# TSAL.net
KiCad netlist of a schematic drawn in Altium Designer
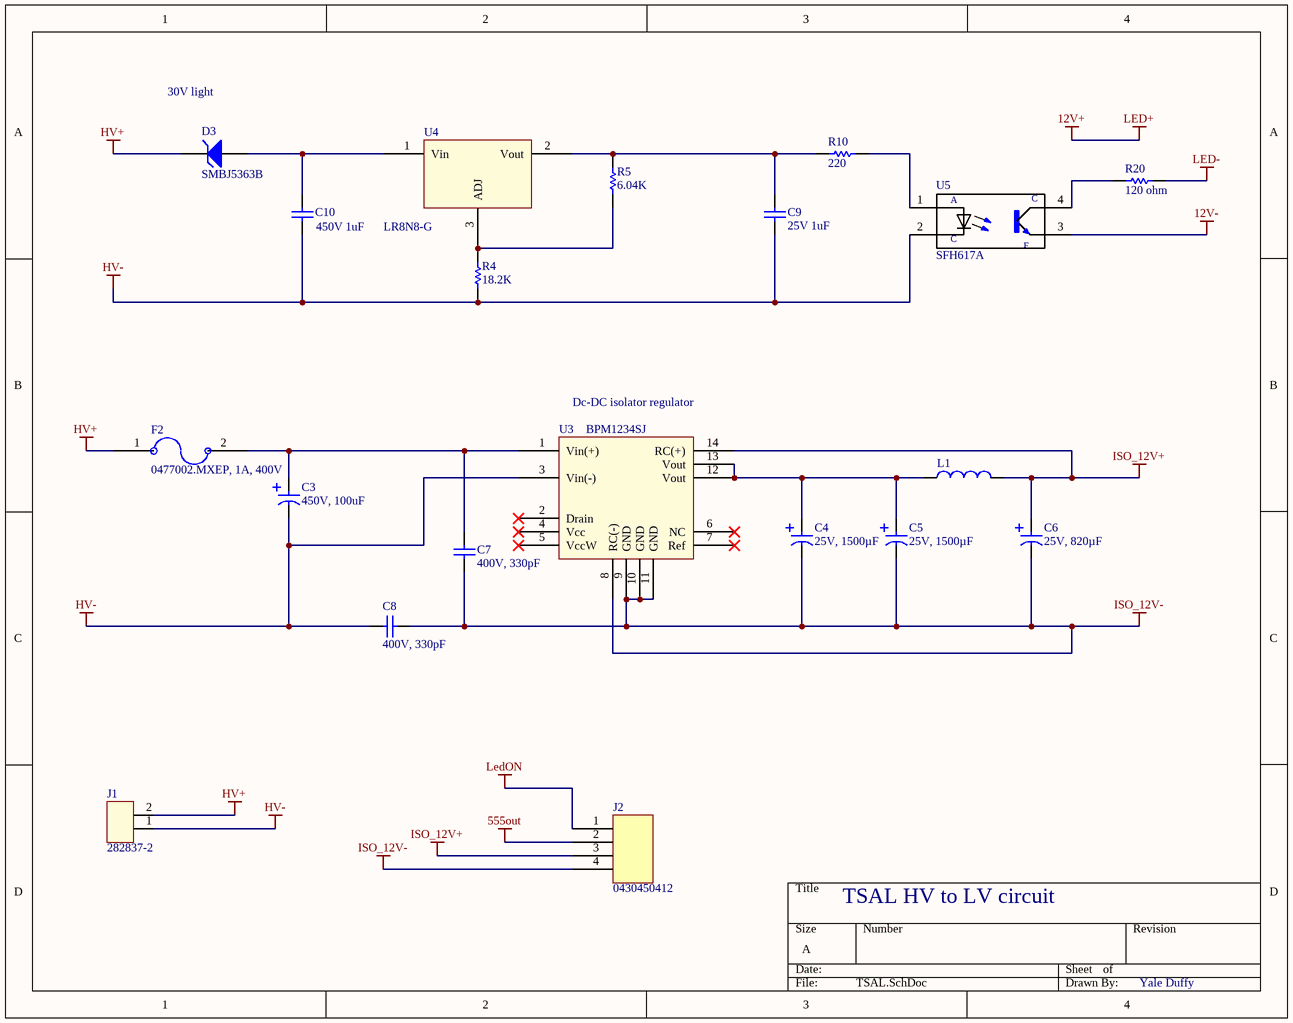
[diagram p0: TSAL.SchDoc]

(export (version "E")
  (design (tool "Eeschema 10.0.6"))
  (components
    (comp (ref "C3")
      (value "450V, 100uF")
      (footprint "450BXW100MEFR18X30")
      (description "Capacitors, Radial, Can, 100µF 450V Aluminum")
      (libsource (lib "schematic") (part "450BXW100MEFR18X30"))
    )
    (comp (ref "C4")
      (value "25V, 1500µF")
      (footprint "25ZLS1500MEFC12.5X20")
      (description "Capacitors, Aluminum Electrolytic, Radial, Can, 1500µF, 25V")
      (libsource (lib "schematic") (part "25ZLS1500MEFC12.5X20"))
    )
    (comp (ref "C5")
      (value "25V, 1500µF")
      (footprint "25ZLS1500MEFC12.5X20")
      (description "Capacitors, Aluminum Electrolytic, Radial, Can, 1500µF, 25V")
      (libsource (lib "schematic") (part "25ZLS1500MEFC12.5X20"))
    )
    (comp (ref "C6")
      (value "25V, 820µF")
      (footprint "ESY827M025AH5AA")
      (description "Capacitors Radial, Can, 820µF 25V Aluminum Electrolytic, 23mOhm @ 100kHz 4000 Hrs @ 105°C")
      (libsource (lib "schematic") (part "ESY827M025AH5AA"))
    )
    (comp (ref "C7")
      (value "400V, 330pF")
      (footprint "DE2B3SA331KN3AY02F")
      (description "Capacitor, 330pF ±10% 400VAC Ceramic Capacitor B Radial, Disc")
      (libsource (lib "schematic") (part "DE2B3SA331KN3AY02F"))
    )
    (comp (ref "C8")
      (value "400V, 330pF")
      (footprint "DE2B3SA331KN3AY02F")
      (description "Capacitor, 330pF ±10% 400VAC Ceramic Capacitor B Radial, Disc")
      (libsource (lib "schematic") (part "DE2B3SA331KN3AY02F"))
    )
    (comp (ref "C9")
      (value "25V 1uF")
      (footprint "C0603C105K3RACTU")
      (description "Capacitor, Ceramic, 1 uF, 25 V, ±10% SMT, 0603")
      (libsource (lib "schematic") (part "C0603C105K3RACTU"))
    )
    (comp (ref "C10")
      (value "450V 1uF")
      (footprint "CKG57KX7T2W105K335JH")
      (description "Decoupling capacitor")
      (libsource (lib "schematic") (part "CKG57KX7T2W105K335JH"))
    )
    (comp (ref "D3")
      (value "SMBJ5363B")
      (footprint "214AA")
      (description "Diode Zener 30V 5W ±5% Surface Mount DO-214AA (SMB)")
      (libsource (lib "schematic") (part "SMBJ5363B"))
    )
    (comp (ref "F2")
      (value "0477002.MXEP, 1A, 400V")
      (footprint "0477002.MXEP")
      (description "Fuse, 2A 500V AC 400V DC Fuse Cartridge, Ceramic Through Hole 5mm x 20mm (Axial)")
      (libsource (lib "schematic") (part "0477002.MXEP"))
    )
    (comp (ref "J1")
      (value "282837-2")
      (footprint "282837-2")
      (description "Connector Terminal Blocks Receptacle 2 Position 5.08mm Solder Straight Thru-Hole 13.5A/Contact")
      (libsource (lib "schematic") (part "282837-2"))
    )
    (comp (ref "J2")
      (value "0430450412")
      (footprint "0430450412")
      (description "Connector Header Through Hole 4 position 0.118\" (3.00mm)")
      (libsource (lib "schematic") (part "0430450412"))
    )
    (comp (ref "L1")
      (value "1267AY-2R2N=P3")
      (footprint "1267AY2R2NP3")
      (description "Shielded Wirewound Inductor, 2.2µH ,7.4A 13.2mOhm Max Nonstandard")
      (libsource (lib "schematic") (part "1267AY-2R2N=P3"))
    )
    (comp (ref "R4")
      (value "18.2K")
      (footprint "Resistor 0603")
      (description "Resistor, 18.2K ohms, 0603, SMD")
      (libsource (lib "schematic") (part "ERJ-3EKF1822V"))
    )
    (comp (ref "R5")
      (value "6.04K")
      (footprint "Resistor 0603")
      (libsource (lib "schematic") (part "ERJ-3EKF6041V"))
    )
    (comp (ref "R10")
      (value "220")
      (footprint "Resistor 0603")
      (description "Resistor, 220 ohm, 0603")
      (libsource (lib "schematic") (part "ERJ-3EKF2200V"))
    )
    (comp (ref "R20")
      (value "120 ohm")
      (footprint "Resistor 0603")
      (description "Resistor, 120 ohms, 0603, SMD")
      (libsource (lib "schematic") (part "ERJ-3EKF1200V"))
    )
    (comp (ref "U3")
      (value "BPM1234SJ")
      (footprint "BPM1234SJ")
      (description "Isolated DC-DC converters, 12 V, 3.4A")
      (libsource (lib "schematic") (part "BPM1234SJ"))
    )
    (comp (ref "U4")
      (value "LR8N8-G")
      (footprint "TO-243AA(SOT-89-3)")
      (description "Voltage Regulator, Linear, input max 480V, output 1.2V - 440V, TO-243AA , SMD")
      (libsource (lib "schematic") (part "LR8N8-G"))
    )
    (comp (ref "U5")
      (value "SFH617A")
      (footprint "SFH617A")
      (description "opto-Isolator")
      (libsource (lib "schematic") (part "SFH617A"))
    )
  )
  (nets
    (net (code "2") (name "12V-") (class "Default")
      (node (ref "U5") (pin "3") (pinfunction "E_3") (pintype "passive"))
    )
    (net (code "3") (name "555out") (class "Default")
      (node (ref "J2") (pin "2") (pinfunction "2_2") (pintype "passive"))
    )
    (net (code "4") (name "HV+") (class "Default")
      (node (ref "D3") (pin "1") (pinfunction "K_1") (pintype "passive"))
      (node (ref "F2") (pin "1") (pinfunction "1_1") (pintype "passive"))
      (node (ref "J1") (pin "2") (pinfunction "2_2") (pintype "passive"))
    )
    (net (code "5") (name "HV-") (class "Default")
      (node (ref "C10") (pin "1") (pintype "passive"))
      (node (ref "C3") (pin "1") (pintype "passive"))
      (node (ref "C8") (pin "2") (pintype "passive"))
      (node (ref "C9") (pin "1") (pintype "passive"))
      (node (ref "J1") (pin "1") (pinfunction "1_1") (pintype "passive"))
      (node (ref "R4") (pin "2") (pinfunction "2_2") (pintype "passive"))
      (node (ref "U3") (pin "3") (pinfunction "Vin(-)_3") (pintype "passive"))
      (node (ref "U5") (pin "2") (pinfunction "C_2") (pintype "passive"))
    )
    (net (code "6") (name "ISO_12V+") (class "Default")
      (node (ref "C6") (pin "2") (pintype "passive"))
      (node (ref "J2") (pin "3") (pinfunction "3_3") (pintype "passive"))
      (node (ref "L1") (pin "2") (pinfunction "2_2") (pintype "passive"))
      (node (ref "U3") (pin "14") (pinfunction "RC(+)_14") (pintype "passive"))
    )
    (net (code "7") (name "ISO_12V-") (class "Default")
      (node (ref "C4") (pin "1") (pintype "passive"))
      (node (ref "C5") (pin "1") (pintype "passive"))
      (node (ref "C6") (pin "1") (pintype "passive"))
      (node (ref "C7") (pin "1") (pintype "passive"))
      (node (ref "C8") (pin "1") (pintype "passive"))
      (node (ref "J2") (pin "4") (pinfunction "4_4") (pintype "passive"))
      (node (ref "U3") (pin "10") (pinfunction "GND_10") (pintype "passive"))
      (node (ref "U3") (pin "11") (pinfunction "GND_11") (pintype "passive"))
      (node (ref "U3") (pin "8") (pinfunction "RC(-)_8") (pintype "passive"))
      (node (ref "U3") (pin "9") (pinfunction "GND_9") (pintype "passive"))
    )
    (net (code "8") (name "LED-") (class "Default")
      (node (ref "R20") (pin "2") (pinfunction "2_2") (pintype "passive"))
    )
    (net (code "9") (name "LedON") (class "Default")
      (node (ref "J2") (pin "1") (pinfunction "1_1") (pintype "passive"))
    )
    (net (code "10") (name "Net-(C4-Pad2)") (class "Default")
      (node (ref "C4") (pin "2") (pintype "passive"))
      (node (ref "C5") (pin "2") (pintype "passive"))
      (node (ref "L1") (pin "1") (pinfunction "1_1") (pintype "passive"))
      (node (ref "U3") (pin "12") (pinfunction "Vout_12") (pintype "passive"))
      (node (ref "U3") (pin "13") (pinfunction "Vout_13") (pintype "passive"))
    )
    (net (code "11") (name "Net-(D3-A)") (class "Default")
      (node (ref "C10") (pin "2") (pintype "passive"))
      (node (ref "D3") (pin "2") (pinfunction "A_2") (pintype "passive"))
      (node (ref "U4") (pin "1") (pinfunction "Vin_1") (pintype "passive"))
    )
    (net (code "12") (name "Net-(U3-Vin(+))") (class "Default")
      (node (ref "C3") (pin "2") (pintype "passive"))
      (node (ref "C7") (pin "2") (pintype "passive"))
      (node (ref "F2") (pin "2") (pinfunction "2_2") (pintype "passive"))
      (node (ref "U3") (pin "1") (pinfunction "Vin(+)_1") (pintype "passive"))
    )
    (net (code "13") (name "Net-(U4-ADJ)") (class "Default")
      (node (ref "R4") (pin "1") (pinfunction "1_1") (pintype "passive"))
      (node (ref "R5") (pin "2") (pinfunction "2_2") (pintype "passive"))
      (node (ref "U4") (pin "3") (pinfunction "ADJ_3") (pintype "passive"))
    )
    (net (code "14") (name "Net-(U4-Vout)") (class "Default")
      (node (ref "C9") (pin "2") (pintype "passive"))
      (node (ref "R10") (pin "1") (pinfunction "1_1") (pintype "passive"))
      (node (ref "R5") (pin "1") (pinfunction "1_1") (pintype "passive"))
      (node (ref "U4") (pin "2") (pinfunction "Vout_2") (pintype "passive"))
    )
    (net (code "15") (name "Net-(U5-A)") (class "Default")
      (node (ref "R10") (pin "2") (pinfunction "2_2") (pintype "passive"))
      (node (ref "U5") (pin "1") (pinfunction "A_1") (pintype "passive"))
    )
    (net (code "16") (name "Net-(U5-CO)") (class "Default")
      (node (ref "R20") (pin "1") (pinfunction "1_1") (pintype "passive"))
      (node (ref "U5") (pin "4") (pinfunction "CO_4") (pintype "passive"))
    )
    (net (code "17") (name "unconnected-(U3-Drain-Pad2)") (class "Default")
      (node (ref "U3") (pin "2") (pinfunction "Drain_2") (pintype "passive+no_connect"))
    )
    (net (code "18") (name "unconnected-(U3-NC-Pad6)") (class "Default")
      (node (ref "U3") (pin "6") (pinfunction "NC_6") (pintype "passive+no_connect"))
    )
    (net (code "19") (name "unconnected-(U3-Ref-Pad7)") (class "Default")
      (node (ref "U3") (pin "7") (pinfunction "Ref_7") (pintype "passive+no_connect"))
    )
    (net (code "20") (name "unconnected-(U3-Vcc-Pad4)") (class "Default")
      (node (ref "U3") (pin "4") (pinfunction "Vcc_4") (pintype "passive+no_connect"))
    )
    (net (code "21") (name "unconnected-(U3-VccW-Pad5)") (class "Default")
      (node (ref "U3") (pin "5") (pinfunction "VccW_5") (pintype "passive+no_connect"))
    )
  )
)
